# V1b.net
KiCad netlist of a schematic drawn in EAGLE
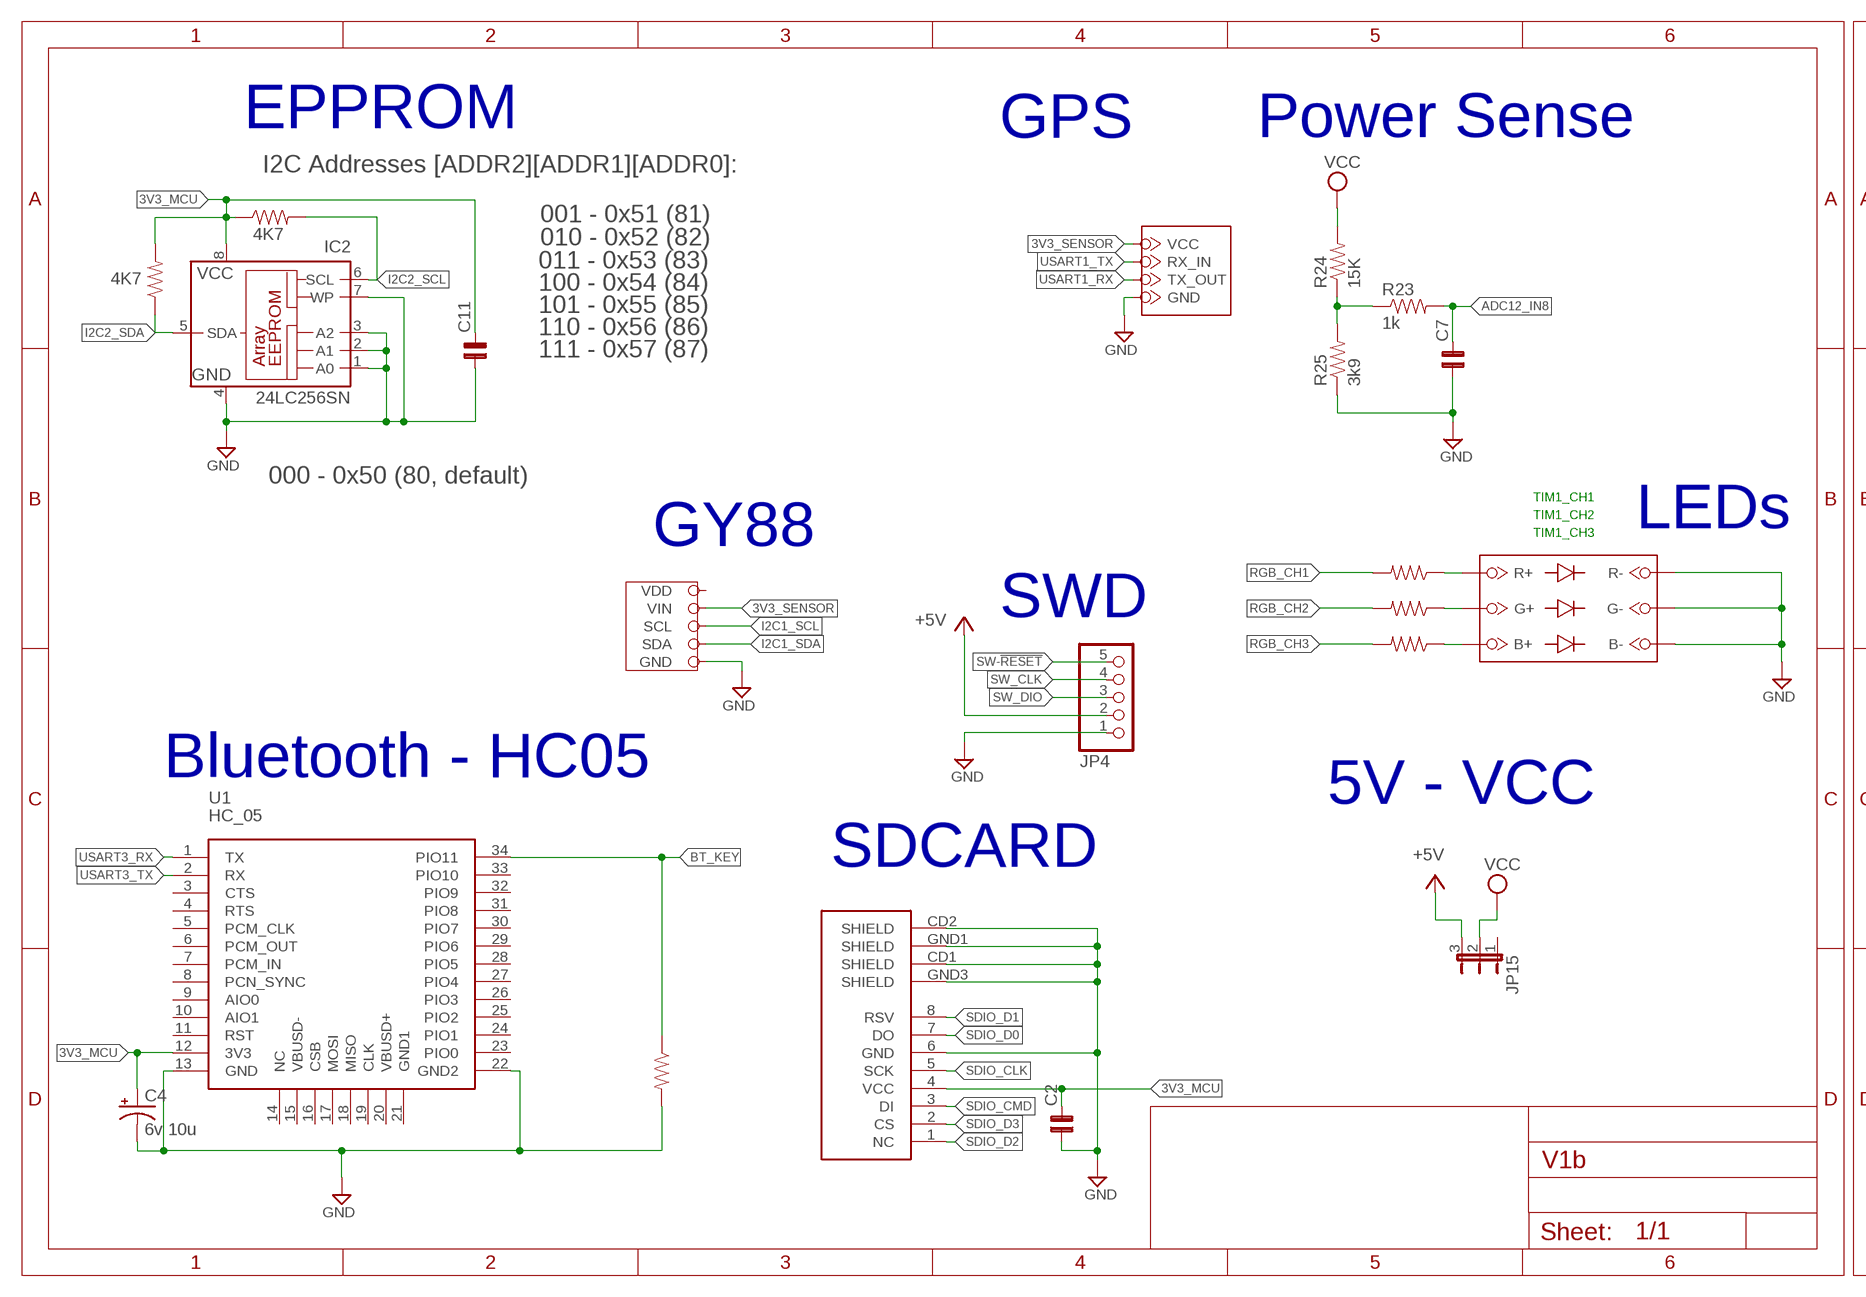
[diagram p0: schematic, sheet 1, part 1 of 2]
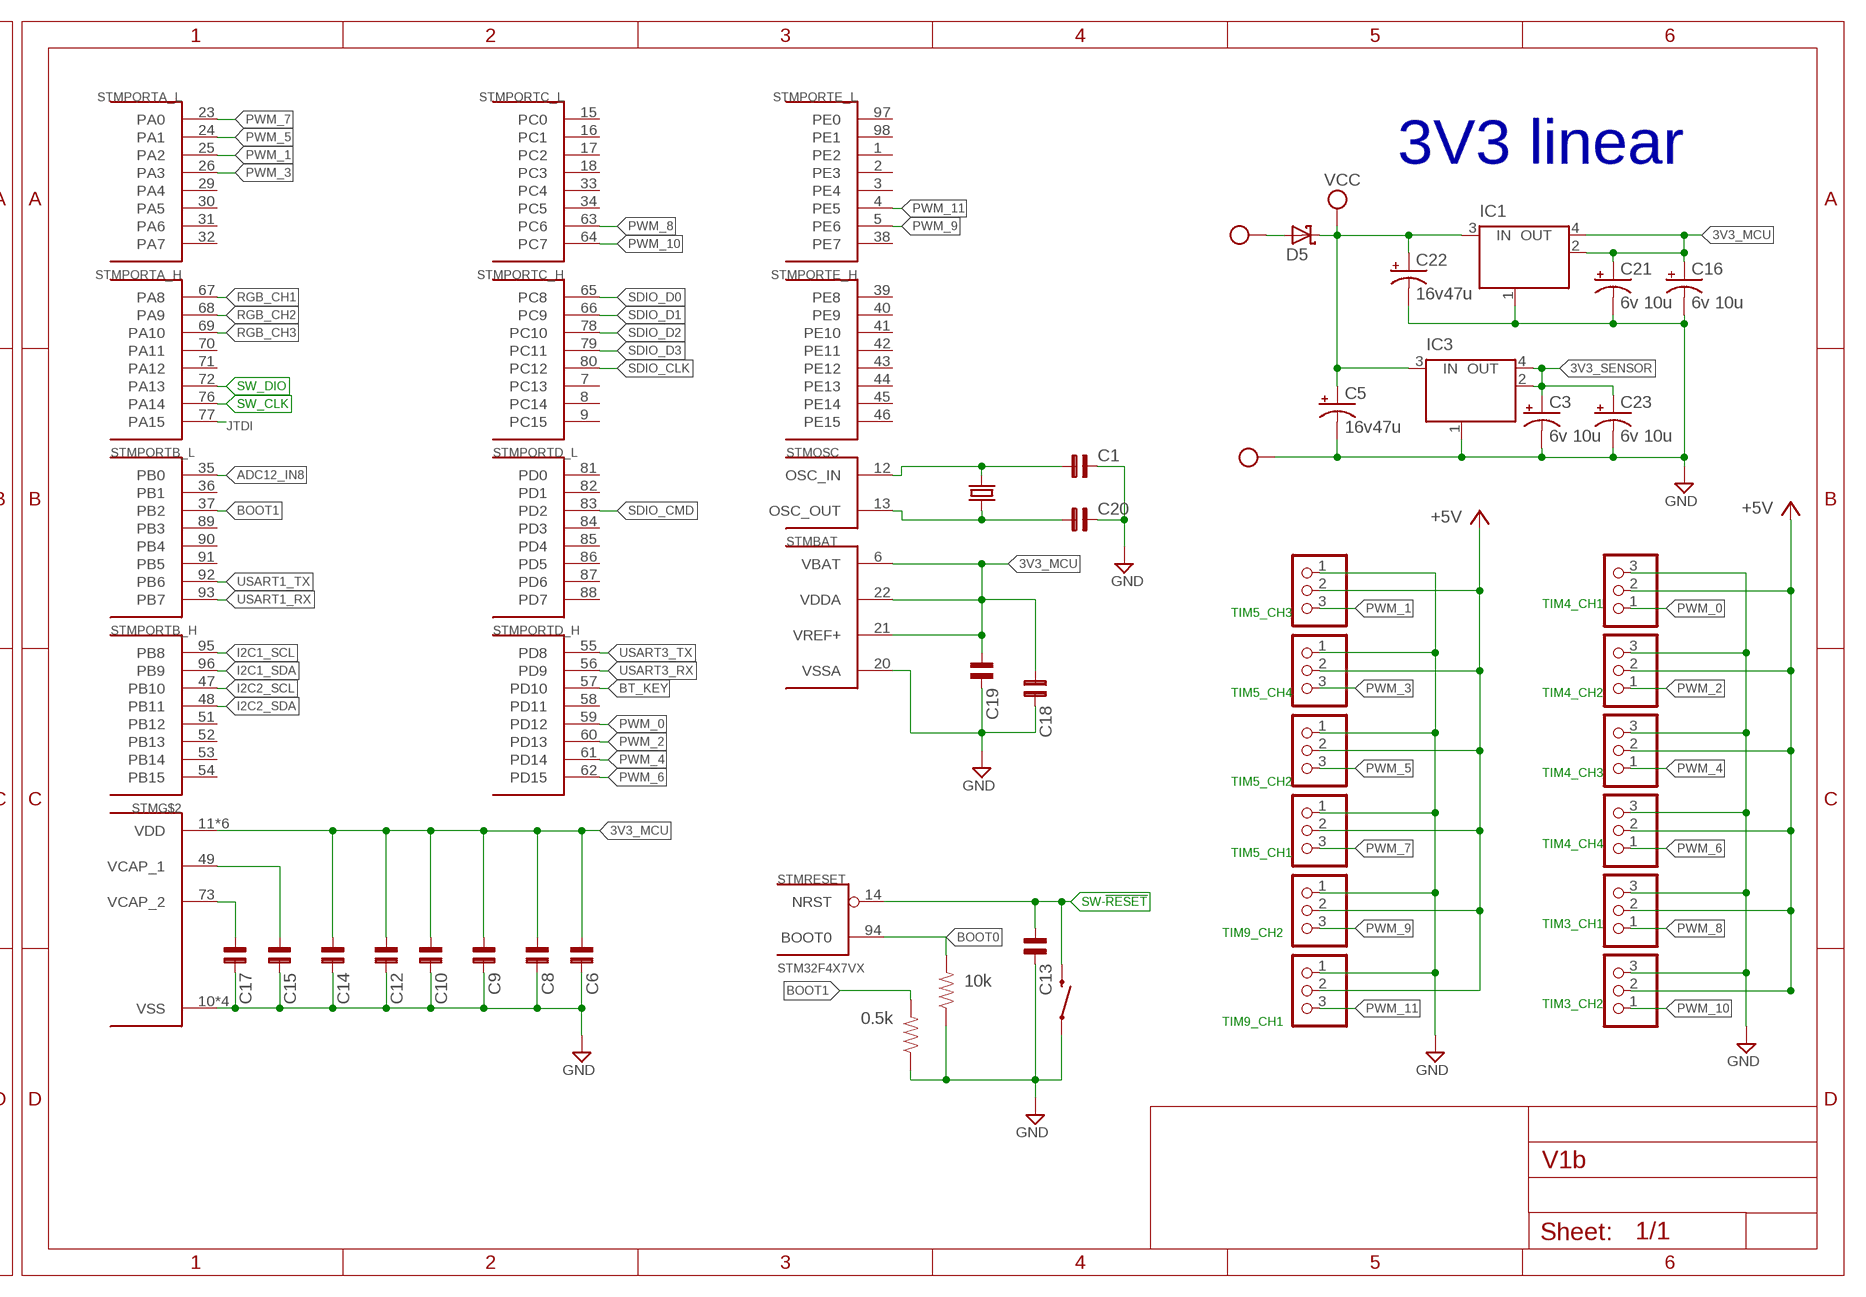
[diagram p1: schematic, sheet 1, part 2 of 2]

(export (version "E")
  (design (tool "Eeschema 10.0.6"))
  (components
    (comp (ref "C1")
      (value "C-NP-SMD-0603")
      (footprint "eagle-import:C-0603")
      (libsource (lib "eagle-import") (part "C-NP-SMD-0603"))
    )
    (comp (ref "C2")
      (value "C-NP-SMD-0603")
      (footprint "eagle-import:C-0603")
      (libsource (lib "eagle-import") (part "C-NP-SMD-0603"))
    )
    (comp (ref "C3")
      (value "6v 10u")
      (footprint "eagle-import:SMC_A")
      (libsource (lib "eagle-import") (part "CPOL-USSMCA"))
    )
    (comp (ref "C4")
      (value "6v 10u")
      (footprint "eagle-import:SMC_A")
      (libsource (lib "eagle-import") (part "CPOL-USSMCA"))
    )
    (comp (ref "C5")
      (value "16v47u")
      (footprint "eagle-import:SMC_C")
      (libsource (lib "eagle-import") (part "CPOL-USSMCC"))
    )
    (comp (ref "C6")
      (value "C-NP-SMD-0603")
      (footprint "eagle-import:C-0603")
      (libsource (lib "eagle-import") (part "C-NP-SMD-0603"))
    )
    (comp (ref "C7")
      (value "C-NP-SMD-0603")
      (footprint "eagle-import:C-0603")
      (libsource (lib "eagle-import") (part "C-NP-SMD-0603"))
    )
    (comp (ref "C8")
      (value "C-NP-SMD-0603")
      (footprint "eagle-import:C-0603")
      (libsource (lib "eagle-import") (part "C-NP-SMD-0603"))
    )
    (comp (ref "C9")
      (value "C-NP-SMD-0603")
      (footprint "eagle-import:C-0603")
      (libsource (lib "eagle-import") (part "C-NP-SMD-0603"))
    )
    (comp (ref "C10")
      (value "C-NP-SMD-0603")
      (footprint "eagle-import:C-0603")
      (libsource (lib "eagle-import") (part "C-NP-SMD-0603"))
    )
    (comp (ref "C11")
      (value "C-NP-SMD-0603")
      (footprint "eagle-import:C-0603")
      (libsource (lib "eagle-import") (part "C-NP-SMD-0603"))
    )
    (comp (ref "C12")
      (value "C-NP-SMD-0603")
      (footprint "eagle-import:C-0603")
      (libsource (lib "eagle-import") (part "C-NP-SMD-0603"))
    )
    (comp (ref "C13")
      (value "C-NP-SMD-0603")
      (footprint "eagle-import:C-0603")
      (libsource (lib "eagle-import") (part "C-NP-SMD-0603"))
    )
    (comp (ref "C14")
      (value "C-NP-SMD-0603")
      (footprint "eagle-import:C-0603")
      (libsource (lib "eagle-import") (part "C-NP-SMD-0603"))
    )
    (comp (ref "C15")
      (value "C-NP-SMD-0603")
      (footprint "eagle-import:C-0603")
      (libsource (lib "eagle-import") (part "C-NP-SMD-0603"))
    )
    (comp (ref "C16")
      (value "6v 10u")
      (footprint "eagle-import:SMC_A")
      (libsource (lib "eagle-import") (part "CPOL-USSMCA"))
    )
    (comp (ref "C17")
      (value "C-NP-SMD-0603")
      (footprint "eagle-import:C-0603")
      (libsource (lib "eagle-import") (part "C-NP-SMD-0603"))
    )
    (comp (ref "C18")
      (value "C-NP-SMD-0603")
      (footprint "eagle-import:C-0603")
      (libsource (lib "eagle-import") (part "C-NP-SMD-0603"))
    )
    (comp (ref "C19")
      (value "C-NP-SMD-0603")
      (footprint "eagle-import:C-0603")
      (libsource (lib "eagle-import") (part "C-NP-SMD-0603"))
    )
    (comp (ref "C20")
      (value "C-NP-SMD-0603")
      (footprint "eagle-import:C-0603")
      (libsource (lib "eagle-import") (part "C-NP-SMD-0603"))
    )
    (comp (ref "C21")
      (value "6v 10u")
      (footprint "eagle-import:SMC_A")
      (libsource (lib "eagle-import") (part "CPOL-USSMCA"))
    )
    (comp (ref "C22")
      (value "16v47u")
      (footprint "eagle-import:SMC_C")
      (libsource (lib "eagle-import") (part "CPOL-USSMCC"))
    )
    (comp (ref "C23")
      (value "6v 10u")
      (footprint "eagle-import:SMC_A")
      (libsource (lib "eagle-import") (part "CPOL-USSMCA"))
    )
    (comp (ref "D5")
      (value "MBRS330T3")
      (footprint "eagle-import:SMC")
      (libsource (lib "eagle-import") (part "MBRS30T33"))
    )
    (comp (ref "IC1")
      (value "LINEAR_MC33269ST-3.3T3")
      (footprint "eagle-import:LINEAR_SOT223")
      (libsource (lib "eagle-import") (part "LINEAR_MC33269ST-3.3T3"))
    )
    (comp (ref "IC2")
      (value "24LC256SN")
      (footprint "eagle-import:SO-08")
      (fields (field (name "MF") "MICROCHIP") (field (name "MPN") "24LC256-I/SN"))
      (libsource (lib "eagle-import") (part "24SNLC256"))
    )
    (comp (ref "IC3")
      (value "LINEAR_MC33269ST-3.3T3")
      (footprint "eagle-import:LINEAR_SOT223")
      (libsource (lib "eagle-import") (part "LINEAR_MC33269ST-3.3T3"))
    )
    (comp (ref "JP1")
      (value "PINHD-1X3_2.54-90°")
      (footprint "eagle-import:1X03_90")
      (libsource (lib "eagle-import") (part "PINHD-1X3_2.54-90°"))
    )
    (comp (ref "JP2")
      (value "PINHD-1X3_2.54-90°")
      (footprint "eagle-import:1X03_90")
      (libsource (lib "eagle-import") (part "PINHD-1X3_2.54-90°"))
    )
    (comp (ref "JP4")
      (value "PINHD-1X5_2.54-90°")
      (footprint "eagle-import:1X05_90")
      (libsource (lib "eagle-import") (part "PINHD-1X5_2.54-90°"))
    )
    (comp (ref "JP5")
      (value "PINHD-1X3_2.54-90°")
      (footprint "eagle-import:1X03_90")
      (libsource (lib "eagle-import") (part "PINHD-1X3_2.54-90°"))
    )
    (comp (ref "JP6")
      (value "PINHD-1X3_2.54-90°")
      (footprint "eagle-import:1X03_90")
      (libsource (lib "eagle-import") (part "PINHD-1X3_2.54-90°"))
    )
    (comp (ref "JP7")
      (value "PINHD-1X3_2.54-90°")
      (footprint "eagle-import:1X03_90")
      (libsource (lib "eagle-import") (part "PINHD-1X3_2.54-90°"))
    )
    (comp (ref "JP8")
      (value "PINHD-1X3_2.54-90°")
      (footprint "eagle-import:1X03_90")
      (libsource (lib "eagle-import") (part "PINHD-1X3_2.54-90°"))
    )
    (comp (ref "JP9")
      (value "PINHD-1X3_2.54-90°")
      (footprint "eagle-import:1X03_90")
      (libsource (lib "eagle-import") (part "PINHD-1X3_2.54-90°"))
    )
    (comp (ref "JP10")
      (value "PINHD-1X3_2.54-90°")
      (footprint "eagle-import:1X03_90")
      (libsource (lib "eagle-import") (part "PINHD-1X3_2.54-90°"))
    )
    (comp (ref "JP11")
      (value "PINHD-1X3_2.54-90°")
      (footprint "eagle-import:1X03_90")
      (libsource (lib "eagle-import") (part "PINHD-1X3_2.54-90°"))
    )
    (comp (ref "JP12")
      (value "PINHD-1X3_2.54-90°")
      (footprint "eagle-import:1X03_90")
      (libsource (lib "eagle-import") (part "PINHD-1X3_2.54-90°"))
    )
    (comp (ref "JP13")
      (value "PINHD-1X3_2.54-90°")
      (footprint "eagle-import:1X03_90")
      (libsource (lib "eagle-import") (part "PINHD-1X3_2.54-90°"))
    )
    (comp (ref "JP14")
      (value "PINHD-1X3_2.54-90°")
      (footprint "eagle-import:1X03_90")
      (libsource (lib "eagle-import") (part "PINHD-1X3_2.54-90°"))
    )
    (comp (ref "JP15")
      (value "JP2E")
      (footprint "eagle-import:JP2")
      (libsource (lib "eagle-import") (part "JP2E"))
    )
    (comp (ref "R2")
      (value "10K")
      (footprint "eagle-import:SPARKFUN_0603-RES")
      (libsource (lib "eagle-import") (part "SPARKFUN_RESISTOR0603-RES"))
    )
    (comp (ref "R3")
      (value "10K")
      (footprint "eagle-import:SPARKFUN_0603-RES")
      (libsource (lib "eagle-import") (part "SPARKFUN_RESISTOR0603-RES"))
    )
    (comp (ref "R5")
      (value "10K")
      (footprint "eagle-import:SPARKFUN_0603-RES")
      (libsource (lib "eagle-import") (part "SPARKFUN_RESISTOR0603-RES"))
    )
    (comp (ref "R6")
      (value "10K")
      (footprint "eagle-import:SPARKFUN_0603-RES")
      (libsource (lib "eagle-import") (part "SPARKFUN_RESISTOR0603-RES"))
    )
    (comp (ref "R7")
      (value "10k")
      (footprint "eagle-import:SPARKFUN_0603-RES")
      (libsource (lib "eagle-import") (part "SPARKFUN_RESISTOR0603-RES"))
    )
    (comp (ref "R8")
      (value "0.5k")
      (footprint "eagle-import:SPARKFUN_0603-RES")
      (libsource (lib "eagle-import") (part "SPARKFUN_RESISTOR0603-RES"))
    )
    (comp (ref "R15")
      (value "4K7")
      (footprint "eagle-import:SPARKFUN_0603-RES")
      (libsource (lib "eagle-import") (part "SPARKFUN_RESISTOR0603-RES"))
    )
    (comp (ref "R16")
      (value "4K7")
      (footprint "eagle-import:SPARKFUN_0603-RES")
      (libsource (lib "eagle-import") (part "SPARKFUN_RESISTOR0603-RES"))
    )
    (comp (ref "R23")
      (value "1k")
      (footprint "eagle-import:SPARKFUN_0603-RES")
      (libsource (lib "eagle-import") (part "SPARKFUN_RESISTOR0603-RES"))
    )
    (comp (ref "R24")
      (value "15K")
      (footprint "eagle-import:SPARKFUN_0603-RES")
      (libsource (lib "eagle-import") (part "SPARKFUN_RESISTOR0603-RES"))
    )
    (comp (ref "R25")
      (value "3k9")
      (footprint "eagle-import:SPARKFUN_0603-RES")
      (libsource (lib "eagle-import") (part "SPARKFUN_RESISTOR0603-RES"))
    )
    (comp (ref "S1")
      (value "RESET")
      (footprint "eagle-import:TACTILE-SWITCH-1101NE")
      (fields (field (name "PARTNO") "EVQ-P7J01P"))
      (libsource (lib "eagle-import") (part "SWITCH-MOMENTARY-2-SMD-1101NE"))
    )
    (comp (ref "SDCARD2")
      (value "microSD Socket")
      (footprint "eagle-import:MICRO-SD-SOCKET-PP")
      (libsource (lib "eagle-import") (part "USD-SOCKETNEW"))
    )
    (comp (ref "STM")
      (value "STM32F4X7VX")
      (footprint "eagle-import:TQFP100")
      (fields (field (name "PARTNO") "STM32F427VI"))
      (libsource (lib "eagle-import") (part "STM32F4X7VX"))
    )
    (comp (ref "U$1")
      (value "GY-88")
      (footprint "eagle-import:BREAKOUT")
      (libsource (lib "eagle-import") (part "GY-88"))
    )
    (comp (ref "U$8")
      (value "RGB_LED")
      (footprint "eagle-import:SMD")
      (libsource (lib "eagle-import") (part "RGB_LED"))
    )
    (comp (ref "U$10")
      (value "GPS_MODULE")
      (footprint "eagle-import:23X30")
      (libsource (lib "eagle-import") (part "GPS_MODULE"))
    )
    (comp (ref "U1")
      (value "HC_05")
      (footprint "eagle-import:BLUETOOTH_SMD")
      (libsource (lib "eagle-import") (part "HC_05"))
    )
    (comp (ref "X1")
      (value "MKDSN1,5/2-5,08")
      (footprint "eagle-import:MKDSN1,5_2-5,08")
      (fields (field (name "MPN") "MKDSN 1,5/2-5.08"))
      (libsource (lib "eagle-import") (part "MKDSN1,5/2-5,08"))
    )
    (comp (ref "Y1")
      (value "CRYSTALHC49US")
      (footprint "eagle-import:HC49US")
      (libsource (lib "eagle-import") (part "CRYSTALHC49US"))
    )
  )
  (nets
    (net (code "1") (name "+5V") (class "Default")
      (node (ref "JP1") (pin "2") (pinfunction "2_2") (pintype "passive"))
      (node (ref "JP10") (pin "2") (pinfunction "2_2") (pintype "passive"))
      (node (ref "JP11") (pin "2") (pinfunction "2_2") (pintype "passive"))
      (node (ref "JP12") (pin "2") (pinfunction "2_2") (pintype "passive"))
      (node (ref "JP13") (pin "2") (pinfunction "2_2") (pintype "passive"))
      (node (ref "JP14") (pin "2") (pinfunction "2_2") (pintype "passive"))
      (node (ref "JP15") (pin "3") (pinfunction "3_3") (pintype "passive"))
      (node (ref "JP2") (pin "2") (pinfunction "2_2") (pintype "passive"))
      (node (ref "JP4") (pin "2") (pinfunction "2_2") (pintype "passive"))
      (node (ref "JP5") (pin "2") (pinfunction "2_2") (pintype "passive"))
      (node (ref "JP6") (pin "2") (pinfunction "2_2") (pintype "passive"))
      (node (ref "JP7") (pin "2") (pinfunction "2_2") (pintype "passive"))
      (node (ref "JP8") (pin "2") (pinfunction "2_2") (pintype "passive"))
      (node (ref "JP9") (pin "2") (pinfunction "2_2") (pintype "passive"))
    )
    (net (code "2") (name "/JTDI") (class "Default")
      (node (ref "STM") (pin "77") (pinfunction "PA15_77") (pintype "bidirectional"))
    )
    (net (code "3") (name "/SW-~{RESET}") (class "Default")
      (node (ref "C13") (pin "1") (pinfunction "1_1") (pintype "passive"))
      (node (ref "JP4") (pin "5") (pinfunction "5_5") (pintype "passive"))
      (node (ref "S1") (pin "P$2") (pinfunction "2_P$2") (pintype "passive"))
      (node (ref "STM") (pin "14") (pinfunction "NRST_14") (pintype "input"))
    )
    (net (code "4") (name "3V3_MCU") (class "Default")
      (node (ref "C10") (pin "1") (pinfunction "1_1") (pintype "passive"))
      (node (ref "C11") (pin "2") (pinfunction "2_2") (pintype "passive"))
      (node (ref "C12") (pin "1") (pinfunction "1_1") (pintype "passive"))
      (node (ref "C14") (pin "1") (pinfunction "1_1") (pintype "passive"))
      (node (ref "C16") (pin "+") (pinfunction "+_+") (pintype "passive"))
      (node (ref "C18") (pin "1") (pinfunction "1_1") (pintype "passive"))
      (node (ref "C19") (pin "1") (pinfunction "1_1") (pintype "passive"))
      (node (ref "C2") (pin "2") (pinfunction "2_2") (pintype "passive"))
      (node (ref "C21") (pin "+") (pinfunction "+_+") (pintype "passive"))
      (node (ref "C4") (pin "+") (pinfunction "+_+") (pintype "passive"))
      (node (ref "C6") (pin "1") (pinfunction "1_1") (pintype "passive"))
      (node (ref "C8") (pin "1") (pinfunction "1_1") (pintype "passive"))
      (node (ref "C9") (pin "1") (pinfunction "1_1") (pintype "passive"))
      (node (ref "IC1") (pin "2") (pinfunction "OUT_2") (pintype "passive"))
      (node (ref "IC1") (pin "4") (pinfunction "OUT_4") (pintype "passive"))
      (node (ref "IC2") (pin "8") (pinfunction "VCC_8") (pintype "power_in"))
      (node (ref "R15") (pin "1") (pinfunction "1_1") (pintype "passive"))
      (node (ref "R16") (pin "2") (pinfunction "2_2") (pintype "passive"))
      (node (ref "SDCARD2") (pin "4") (pinfunction "VCC_4") (pintype "bidirectional"))
      (node (ref "STM") (pin "100") (pinfunction "VDD_100") (pintype "power_in"))
      (node (ref "STM") (pin "11") (pinfunction "VDD_11") (pintype "power_in"))
      (node (ref "STM") (pin "19") (pinfunction "VDD_19") (pintype "power_in"))
      (node (ref "STM") (pin "21") (pinfunction "VREF+_21") (pintype "input"))
      (node (ref "STM") (pin "22") (pinfunction "VDDA_22") (pintype "power_in"))
      (node (ref "STM") (pin "28") (pinfunction "VDD_28") (pintype "power_in"))
      (node (ref "STM") (pin "50") (pinfunction "VDD_50") (pintype "power_in"))
      (node (ref "STM") (pin "6") (pinfunction "VBAT_6") (pintype "power_in"))
      (node (ref "STM") (pin "75") (pinfunction "VDD_75") (pintype "power_in"))
      (node (ref "U1") (pin "12") (pinfunction "3V3_12") (pintype "bidirectional"))
    )
    (net (code "5") (name "3V3_SENSOR") (class "Default")
      (node (ref "C23") (pin "+") (pinfunction "+_+") (pintype "passive"))
      (node (ref "C3") (pin "+") (pinfunction "+_+") (pintype "passive"))
      (node (ref "IC3") (pin "2") (pinfunction "OUT_2") (pintype "passive"))
      (node (ref "IC3") (pin "4") (pinfunction "OUT_4") (pintype "passive"))
      (node (ref "U$1") (pin "2") (pinfunction "VIN_2") (pintype "bidirectional"))
      (node (ref "U$10") (pin "4") (pinfunction "VCC_4") (pintype "bidirectional"))
    )
    (net (code "6") (name "ADC12_IN8") (class "Default")
      (node (ref "C7") (pin "2") (pinfunction "2_2") (pintype "passive"))
      (node (ref "R23") (pin "2") (pinfunction "2_2") (pintype "passive"))
      (node (ref "STM") (pin "35") (pinfunction "PB0_35") (pintype "bidirectional"))
    )
    (net (code "7") (name "BOOT0") (class "Default")
      (node (ref "R7") (pin "2") (pinfunction "2_2") (pintype "passive"))
      (node (ref "STM") (pin "94") (pinfunction "BOOT0_94") (pintype "input"))
    )
    (net (code "8") (name "BOOT1") (class "Default")
      (node (ref "R8") (pin "2") (pinfunction "2_2") (pintype "passive"))
      (node (ref "STM") (pin "37") (pinfunction "PB2_37") (pintype "bidirectional"))
    )
    (net (code "9") (name "BT_KEY") (class "Default")
      (node (ref "R5") (pin "1") (pinfunction "1_1") (pintype "passive"))
      (node (ref "STM") (pin "57") (pinfunction "PD10_57") (pintype "bidirectional"))
      (node (ref "U1") (pin "34") (pinfunction "PIO11_34") (pintype "bidirectional"))
    )
    (net (code "10") (name "GND") (class "Default")
      (node (ref "C1") (pin "2") (pinfunction "2_2") (pintype "passive"))
      (node (ref "C10") (pin "2") (pinfunction "2_2") (pintype "passive"))
      (node (ref "C11") (pin "1") (pinfunction "1_1") (pintype "passive"))
      (node (ref "C12") (pin "2") (pinfunction "2_2") (pintype "passive"))
      (node (ref "C13") (pin "2") (pinfunction "2_2") (pintype "passive"))
      (node (ref "C14") (pin "2") (pinfunction "2_2") (pintype "passive"))
      (node (ref "C15") (pin "2") (pinfunction "2_2") (pintype "passive"))
      (node (ref "C16") (pin "-") (pinfunction "-_-") (pintype "passive"))
      (node (ref "C17") (pin "2") (pinfunction "2_2") (pintype "passive"))
      (node (ref "C18") (pin "2") (pinfunction "2_2") (pintype "passive"))
      (node (ref "C19") (pin "2") (pinfunction "2_2") (pintype "passive"))
      (node (ref "C2") (pin "1") (pinfunction "1_1") (pintype "passive"))
      (node (ref "C20") (pin "2") (pinfunction "2_2") (pintype "passive"))
      (node (ref "C21") (pin "-") (pinfunction "-_-") (pintype "passive"))
      (node (ref "C22") (pin "-") (pinfunction "-_-") (pintype "passive"))
      (node (ref "C23") (pin "-") (pinfunction "-_-") (pintype "passive"))
      (node (ref "C3") (pin "-") (pinfunction "-_-") (pintype "passive"))
      (node (ref "C4") (pin "-") (pinfunction "-_-") (pintype "passive"))
      (node (ref "C5") (pin "-") (pinfunction "-_-") (pintype "passive"))
      (node (ref "C6") (pin "2") (pinfunction "2_2") (pintype "passive"))
      (node (ref "C7") (pin "1") (pinfunction "1_1") (pintype "passive"))
      (node (ref "C8") (pin "2") (pinfunction "2_2") (pintype "passive"))
      (node (ref "C9") (pin "2") (pinfunction "2_2") (pintype "passive"))
      (node (ref "IC1") (pin "1") (pinfunction "GND/ADJ_1") (pintype "input"))
      (node (ref "IC2") (pin "1") (pinfunction "A0_1") (pintype "input"))
      (node (ref "IC2") (pin "2") (pinfunction "A1_2") (pintype "input"))
      (node (ref "IC2") (pin "3") (pinfunction "A2_3") (pintype "input"))
      (node (ref "IC2") (pin "4") (pinfunction "GND_4") (pintype "power_in"))
      (node (ref "IC2") (pin "7") (pinfunction "WP_7") (pintype "input"))
      (node (ref "IC3") (pin "1") (pinfunction "GND/ADJ_1") (pintype "input"))
      (node (ref "JP1") (pin "1") (pinfunction "1_1") (pintype "passive"))
      (node (ref "JP10") (pin "3") (pinfunction "3_3") (pintype "passive"))
      (node (ref "JP11") (pin "1") (pinfunction "1_1") (pintype "passive"))
      (node (ref "JP12") (pin "3") (pinfunction "3_3") (pintype "passive"))
      (node (ref "JP13") (pin "3") (pinfunction "3_3") (pintype "passive"))
      (node (ref "JP14") (pin "3") (pinfunction "3_3") (pintype "passive"))
      (node (ref "JP2") (pin "1") (pinfunction "1_1") (pintype "passive"))
      (node (ref "JP4") (pin "1") (pinfunction "1_1") (pintype "passive"))
      (node (ref "JP5") (pin "1") (pinfunction "1_1") (pintype "passive"))
      (node (ref "JP6") (pin "1") (pinfunction "1_1") (pintype "passive"))
      (node (ref "JP7") (pin "3") (pinfunction "3_3") (pintype "passive"))
      (node (ref "JP8") (pin "1") (pinfunction "1_1") (pintype "passive"))
      (node (ref "JP9") (pin "3") (pinfunction "3_3") (pintype "passive"))
      (node (ref "R25") (pin "1") (pinfunction "1_1") (pintype "passive"))
      (node (ref "R5") (pin "2") (pinfunction "2_2") (pintype "passive"))
      (node (ref "R7") (pin "1") (pinfunction "1_1") (pintype "passive"))
      (node (ref "R8") (pin "1") (pinfunction "1_1") (pintype "passive"))
      (node (ref "S1") (pin "P$1") (pinfunction "1_P$1") (pintype "passive"))
      (node (ref "SDCARD2") (pin "6") (pinfunction "GND_6") (pintype "bidirectional"))
      (node (ref "SDCARD2") (pin "CD1") (pinfunction "SHIELD_CD1") (pintype "bidirectional"))
      (node (ref "SDCARD2") (pin "CD2") (pinfunction "SHIELD_CD2") (pintype "bidirectional"))
      (node (ref "SDCARD2") (pin "GND1") (pinfunction "SHIELD_GND1") (pintype "bidirectional"))
      (node (ref "SDCARD2") (pin "GND3") (pinfunction "SHIELD_GND3") (pintype "bidirectional"))
      (node (ref "STM") (pin "10") (pinfunction "VSS_10") (pintype "power_in"))
      (node (ref "STM") (pin "20") (pinfunction "VSSA_20") (pintype "power_in"))
      (node (ref "STM") (pin "27") (pinfunction "VSS_27") (pintype "power_in"))
      (node (ref "STM") (pin "74") (pinfunction "VSS_74") (pintype "power_in"))
      (node (ref "STM") (pin "99") (pinfunction "VSS_99") (pintype "power_in"))
      (node (ref "U$1") (pin "3") (pinfunction "GND_3") (pintype "bidirectional"))
      (node (ref "U$10") (pin "1") (pinfunction "GND_1") (pintype "bidirectional"))
      (node (ref "U$8") (pin "B-") (pinfunction "B-_B-") (pintype "bidirectional"))
      (node (ref "U$8") (pin "G-") (pinfunction "G-_G-") (pintype "bidirectional"))
      (node (ref "U$8") (pin "R-") (pinfunction "R-_R-") (pintype "bidirectional"))
      (node (ref "U1") (pin "13") (pinfunction "GND_13") (pintype "bidirectional"))
      (node (ref "U1") (pin "22") (pinfunction "GND2_22") (pintype "bidirectional"))
      (node (ref "X1") (pin "2") (pinfunction "KL_2") (pintype "passive"))
    )
    (net (code "11") (name "I2C1_SCL") (class "Default")
      (node (ref "STM") (pin "95") (pinfunction "PB8_95") (pintype "bidirectional"))
      (node (ref "U$1") (pin "4") (pinfunction "SCL_4") (pintype "bidirectional"))
    )
    (net (code "12") (name "I2C1_SDA") (class "Default")
      (node (ref "STM") (pin "96") (pinfunction "PB9_96") (pintype "bidirectional"))
      (node (ref "U$1") (pin "5") (pinfunction "SDA_5") (pintype "bidirectional"))
    )
    (net (code "13") (name "I2C2_SCL") (class "Default")
      (node (ref "IC2") (pin "6") (pinfunction "SCL_6") (pintype "input"))
      (node (ref "R15") (pin "2") (pinfunction "2_2") (pintype "passive"))
      (node (ref "STM") (pin "47") (pinfunction "PB10_47") (pintype "bidirectional"))
    )
    (net (code "14") (name "I2C2_SDA") (class "Default")
      (node (ref "IC2") (pin "5") (pinfunction "SDA_5") (pintype "bidirectional"))
      (node (ref "R16") (pin "1") (pinfunction "1_1") (pintype "passive"))
      (node (ref "STM") (pin "48") (pinfunction "PB11_48") (pintype "bidirectional"))
    )
    (net (code "15") (name "Net-(R2-Pad1)") (class "Default")
      (node (ref "R2") (pin "1") (pinfunction "1_1") (pintype "passive"))
      (node (ref "U$8") (pin "B+") (pinfunction "B+_B+") (pintype "bidirectional"))
    )
    (net (code "16") (name "Net-(R3-Pad1)") (class "Default")
      (node (ref "R3") (pin "1") (pinfunction "1_1") (pintype "passive"))
      (node (ref "U$8") (pin "G+") (pinfunction "G+_G+") (pintype "bidirectional"))
    )
    (net (code "17") (name "Net-(R6-Pad1)") (class "Default")
      (node (ref "R6") (pin "1") (pinfunction "1_1") (pintype "passive"))
      (node (ref "U$8") (pin "R+") (pinfunction "R+_R+") (pintype "bidirectional"))
    )
    (net (code "18") (name "Net-(R23-Pad1)") (class "Default")
      (node (ref "R23") (pin "1") (pinfunction "1_1") (pintype "passive"))
      (node (ref "R24") (pin "1") (pinfunction "1_1") (pintype "passive"))
      (node (ref "R25") (pin "2") (pinfunction "2_2") (pintype "passive"))
    )
    (net (code "19") (name "Net-(STMB-VCAP_1)") (class "Default")
      (node (ref "C15") (pin "1") (pinfunction "1_1") (pintype "passive"))
      (node (ref "STM") (pin "49") (pinfunction "VCAP_1_49") (pintype "power_in"))
    )
    (net (code "20") (name "Net-(STMB-VCAP_2)") (class "Default")
      (node (ref "C17") (pin "1") (pinfunction "1_1") (pintype "passive"))
      (node (ref "STM") (pin "73") (pinfunction "VCAP_2_73") (pintype "power_in"))
    )
    (net (code "21") (name "Net-(STMC-OSC_IN)") (class "Default")
      (node (ref "C1") (pin "1") (pinfunction "1_1") (pintype "passive"))
      (node (ref "STM") (pin "12") (pinfunction "OSC_IN_12") (pintype "input"))
      (node (ref "Y1") (pin "2") (pinfunction "2_2") (pintype "passive"))
    )
    (net (code "22") (name "Net-(STMC-OSC_OUT)") (class "Default")
      (node (ref "C20") (pin "1") (pinfunction "1_1") (pintype "passive"))
      (node (ref "STM") (pin "13") (pinfunction "OSC_OUT_13") (pintype "output"))
      (node (ref "Y1") (pin "1") (pinfunction "1_1") (pintype "passive"))
    )
    (net (code "23") (name "Net-(X1A-KL)") (class "Default")
      (node (ref "D5") (pin "A") (pinfunction "A_A") (pintype "passive"))
      (node (ref "X1") (pin "1") (pinfunction "KL_1") (pintype "passive"))
    )
    (net (code "24") (name "PWM_0") (class "Default")
      (node (ref "JP7") (pin "1") (pinfunction "1_1") (pintype "passive"))
      (node (ref "STM") (pin "59") (pinfunction "PD12_59") (pintype "bidirectional"))
    )
    (net (code "25") (name "PWM_1") (class "Default")
      (node (ref "JP11") (pin "3") (pinfunction "3_3") (pintype "passive"))
      (node (ref "STM") (pin "25") (pinfunction "PA2_25") (pintype "bidirectional"))
    )
    (net (code "26") (name "PWM_2") (class "Default")
      (node (ref "JP9") (pin "1") (pinfunction "1_1") (pintype "passive"))
      (node (ref "STM") (pin "60") (pinfunction "PD13_60") (pintype "bidirectional"))
    )
    (net (code "27") (name "PWM_3") (class "Default")
      (node (ref "JP6") (pin "3") (pinfunction "3_3") (pintype "passive"))
      (node (ref "STM") (pin "26") (pinfunction "PA3_26") (pintype "bidirectional"))
    )
    (net (code "28") (name "PWM_4") (class "Default")
      (node (ref "JP10") (pin "1") (pinfunction "1_1") (pintype "passive"))
      (node (ref "STM") (pin "61") (pinfunction "PD14_61") (pintype "bidirectional"))
    )
    (net (code "29") (name "PWM_5") (class "Default")
      (node (ref "JP5") (pin "3") (pinfunction "3_3") (pintype "passive"))
      (node (ref "STM") (pin "24") (pinfunction "PA1_24") (pintype "bidirectional"))
    )
    (net (code "30") (name "PWM_6") (class "Default")
      (node (ref "JP12") (pin "1") (pinfunction "1_1") (pintype "passive"))
      (node (ref "STM") (pin "62") (pinfunction "PD15_62") (pintype "bidirectional"))
    )
    (net (code "31") (name "PWM_7") (class "Default")
      (node (ref "JP1") (pin "3") (pinfunction "3_3") (pintype "passive"))
      (node (ref "STM") (pin "23") (pinfunction "PA0_23") (pintype "bidirectional"))
    )
    (net (code "32") (name "PWM_8") (class "Default")
      (node (ref "JP13") (pin "1") (pinfunction "1_1") (pintype "passive"))
      (node (ref "STM") (pin "63") (pinfunction "PC6_63") (pintype "bidirectional"))
    )
    (net (code "33") (name "PWM_9") (class "Default")
      (node (ref "JP8") (pin "3") (pinfunction "3_3") (pintype "passive"))
      (node (ref "STM") (pin "5") (pinfunction "PE6_5") (pintype "bidirectional"))
    )
    (net (code "34") (name "PWM_10") (class "Default")
      (node (ref "JP14") (pin "1") (pinfunction "1_1") (pintype "passive"))
      (node (ref "STM") (pin "64") (pinfunction "PC7_64") (pintype "bidirectional"))
    )
    (net (code "35") (name "PWM_11") (class "Default")
      (node (ref "JP2") (pin "3") (pinfunction "3_3") (pintype "passive"))
      (node (ref "STM") (pin "4") (pinfunction "PE5_4") (pintype "bidirectional"))
    )
    (net (code "36") (name "RGB_CH1") (class "Default")
      (node (ref "R6") (pin "2") (pinfunction "2_2") (pintype "passive"))
      (node (ref "STM") (pin "67") (pinfunction "PA8_67") (pintype "bidirectional"))
    )
    (net (code "37") (name "RGB_CH2") (class "Default")
      (node (ref "R3") (pin "2") (pinfunction "2_2") (pintype "passive"))
      (node (ref "STM") (pin "68") (pinfunction "PA9_68") (pintype "bidirectional"))
    )
    (net (code "38") (name "RGB_CH3") (class "Default")
      (node (ref "R2") (pin "2") (pinfunction "2_2") (pintype "passive"))
      (node (ref "STM") (pin "69") (pinfunction "PA10_69") (pintype "bidirectional"))
    )
    (net (code "39") (name "SDIO_CLK") (class "Default")
      (node (ref "SDCARD2") (pin "5") (pinfunction "SCK_5") (pintype "bidirectional"))
      (node (ref "STM") (pin "80") (pinfunction "PC12_80") (pintype "bidirectional"))
    )
    (net (code "40") (name "SDIO_CMD") (class "Default")
      (node (ref "SDCARD2") (pin "3") (pinfunction "DI_3") (pintype "bidirectional"))
      (node (ref "STM") (pin "83") (pinfunction "PD2_83") (pintype "bidirectional"))
    )
    (net (code "41") (name "SDIO_D0") (class "Default")
      (node (ref "SDCARD2") (pin "7") (pinfunction "DO_7") (pintype "bidirectional"))
      (node (ref "STM") (pin "65") (pinfunction "PC8_65") (pintype "bidirectional"))
    )
    (net (code "42") (name "SDIO_D1") (class "Default")
      (node (ref "SDCARD2") (pin "8") (pinfunction "RSV_8") (pintype "bidirectional"))
      (node (ref "STM") (pin "66") (pinfunction "PC9_66") (pintype "bidirectional"))
    )
    (net (code "43") (name "SDIO_D2") (class "Default")
      (node (ref "SDCARD2") (pin "1") (pinfunction "NC_1") (pintype "bidirectional"))
      (node (ref "STM") (pin "78") (pinfunction "PC10_78") (pintype "bidirectional"))
    )
    (net (code "44") (name "SDIO_D3") (class "Default")
      (node (ref "SDCARD2") (pin "2") (pinfunction "CS_2") (pintype "bidirectional"))
      (node (ref "STM") (pin "79") (pinfunction "PC11_79") (pintype "bidirectional"))
    )
    (net (code "45") (name "SW_CLK") (class "Default")
      (node (ref "JP4") (pin "4") (pinfunction "4_4") (pintype "passive"))
      (node (ref "STM") (pin "76") (pinfunction "PA14_76") (pintype "bidirectional"))
    )
    (net (code "46") (name "SW_DIO") (class "Default")
      (node (ref "JP4") (pin "3") (pinfunction "3_3") (pintype "passive"))
      (node (ref "STM") (pin "72") (pinfunction "PA13_72") (pintype "bidirectional"))
    )
    (net (code "47") (name "USART1_RX") (class "Default")
      (node (ref "STM") (pin "93") (pinfunction "PB7_93") (pintype "bidirectional"))
      (node (ref "U$10") (pin "2") (pinfunction "TX_OUT_2") (pintype "bidirectional"))
    )
    (net (code "48") (name "USART1_TX") (class "Default")
      (node (ref "STM") (pin "92") (pinfunction "PB6_92") (pintype "bidirectional"))
      (node (ref "U$10") (pin "3") (pinfunction "RX_IN_3") (pintype "bidirectional"))
    )
    (net (code "49") (name "USART3_RX") (class "Default")
      (node (ref "STM") (pin "56") (pinfunction "PD9_56") (pintype "bidirectional"))
      (node (ref "U1") (pin "1") (pinfunction "TX_1") (pintype "bidirectional"))
    )
    (net (code "50") (name "USART3_TX") (class "Default")
      (node (ref "STM") (pin "55") (pinfunction "PD8_55") (pintype "bidirectional"))
      (node (ref "U1") (pin "2") (pinfunction "RX_2") (pintype "bidirectional"))
    )
    (net (code "51") (name "VCC") (class "Default")
      (node (ref "C22") (pin "+") (pinfunction "+_+") (pintype "passive"))
      (node (ref "C5") (pin "+") (pinfunction "+_+") (pintype "passive"))
      (node (ref "D5") (pin "C") (pinfunction "C_C") (pintype "passive"))
      (node (ref "IC1") (pin "3") (pinfunction "IN_3") (pintype "input"))
      (node (ref "IC3") (pin "3") (pinfunction "IN_3") (pintype "input"))
      (node (ref "JP15") (pin "2") (pinfunction "2_2") (pintype "passive"))
      (node (ref "R24") (pin "2") (pinfunction "2_2") (pintype "passive"))
    )
    (net (code "52") (name "unconnected-(JP15-Pad1)") (class "Default")
      (node (ref "JP15") (pin "1") (pinfunction "1_1") (pintype "passive"))
    )
    (net (code "53") (name "unconnected-(STMD-PA11-Pad70)") (class "Default")
      (node (ref "STM") (pin "70") (pinfunction "PA11_70") (pintype "bidirectional"))
    )
    (net (code "54") (name "unconnected-(STMD-PA12-Pad71)") (class "Default")
      (node (ref "STM") (pin "71") (pinfunction "PA12_71") (pintype "bidirectional"))
    )
    (net (code "55") (name "unconnected-(STME-PA4-Pad29)") (class "Default")
      (node (ref "STM") (pin "29") (pinfunction "PA4_29") (pintype "bidirectional"))
    )
    (net (code "56") (name "unconnected-(STME-PA5-Pad30)") (class "Default")
      (node (ref "STM") (pin "30") (pinfunction "PA5_30") (pintype "bidirectional"))
    )
    (net (code "57") (name "unconnected-(STME-PA6-Pad31)") (class "Default")
      (node (ref "STM") (pin "31") (pinfunction "PA6_31") (pintype "bidirectional"))
    )
    (net (code "58") (name "unconnected-(STME-PA7-Pad32)") (class "Default")
      (node (ref "STM") (pin "32") (pinfunction "PA7_32") (pintype "bidirectional"))
    )
    (net (code "59") (name "unconnected-(STMF-PB12-Pad51)") (class "Default")
      (node (ref "STM") (pin "51") (pinfunction "PB12_51") (pintype "bidirectional"))
    )
    (net (code "60") (name "unconnected-(STMF-PB13-Pad52)") (class "Default")
      (node (ref "STM") (pin "52") (pinfunction "PB13_52") (pintype "bidirectional"))
    )
    (net (code "61") (name "unconnected-(STMF-PB14-Pad53)") (class "Default")
      (node (ref "STM") (pin "53") (pinfunction "PB14_53") (pintype "bidirectional"))
    )
    (net (code "62") (name "unconnected-(STMF-PB15-Pad54)") (class "Default")
      (node (ref "STM") (pin "54") (pinfunction "PB15_54") (pintype "bidirectional"))
    )
    (net (code "63") (name "unconnected-(STMG-PB1-Pad36)") (class "Default")
      (node (ref "STM") (pin "36") (pinfunction "PB1_36") (pintype "bidirectional"))
    )
    (net (code "64") (name "unconnected-(STMG-PB3-Pad89)") (class "Default")
      (node (ref "STM") (pin "89") (pinfunction "PB3_89") (pintype "bidirectional"))
    )
    (net (code "65") (name "unconnected-(STMG-PB4-Pad90)") (class "Default")
      (node (ref "STM") (pin "90") (pinfunction "PB4_90") (pintype "bidirectional"))
    )
    (net (code "66") (name "unconnected-(STMG-PB5-Pad91)") (class "Default")
      (node (ref "STM") (pin "91") (pinfunction "PB5_91") (pintype "bidirectional"))
    )
    (net (code "67") (name "unconnected-(STMH-PC13-Pad7)") (class "Default")
      (node (ref "STM") (pin "7") (pinfunction "PC13_7") (pintype "bidirectional"))
    )
    (net (code "68") (name "unconnected-(STMH-PC14-Pad8)") (class "Default")
      (node (ref "STM") (pin "8") (pinfunction "PC14_8") (pintype "bidirectional"))
    )
    (net (code "69") (name "unconnected-(STMH-PC15-Pad9)") (class "Default")
      (node (ref "STM") (pin "9") (pinfunction "PC15_9") (pintype "bidirectional"))
    )
    (net (code "70") (name "unconnected-(STMI-PC0-Pad15)") (class "Default")
      (node (ref "STM") (pin "15") (pinfunction "PC0_15") (pintype "bidirectional"))
    )
    (net (code "71") (name "unconnected-(STMI-PC1-Pad16)") (class "Default")
      (node (ref "STM") (pin "16") (pinfunction "PC1_16") (pintype "bidirectional"))
    )
    (net (code "72") (name "unconnected-(STMI-PC2-Pad17)") (class "Default")
      (node (ref "STM") (pin "17") (pinfunction "PC2_17") (pintype "bidirectional"))
    )
    (net (code "73") (name "unconnected-(STMI-PC3-Pad18)") (class "Default")
      (node (ref "STM") (pin "18") (pinfunction "PC3_18") (pintype "bidirectional"))
    )
    (net (code "74") (name "unconnected-(STMI-PC4-Pad33)") (class "Default")
      (node (ref "STM") (pin "33") (pinfunction "PC4_33") (pintype "bidirectional"))
    )
    (net (code "75") (name "unconnected-(STMI-PC5-Pad34)") (class "Default")
      (node (ref "STM") (pin "34") (pinfunction "PC5_34") (pintype "bidirectional"))
    )
    (net (code "76") (name "unconnected-(STMJ-PD11-Pad58)") (class "Default")
      (node (ref "STM") (pin "58") (pinfunction "PD11_58") (pintype "bidirectional"))
    )
    (net (code "77") (name "unconnected-(STMK-PD0-Pad81)") (class "Default")
      (node (ref "STM") (pin "81") (pinfunction "PD0_81") (pintype "bidirectional"))
    )
    (net (code "78") (name "unconnected-(STMK-PD1-Pad82)") (class "Default")
      (node (ref "STM") (pin "82") (pinfunction "PD1_82") (pintype "bidirectional"))
    )
    (net (code "79") (name "unconnected-(STMK-PD3-Pad84)") (class "Default")
      (node (ref "STM") (pin "84") (pinfunction "PD3_84") (pintype "bidirectional"))
    )
    (net (code "80") (name "unconnected-(STMK-PD4-Pad85)") (class "Default")
      (node (ref "STM") (pin "85") (pinfunction "PD4_85") (pintype "bidirectional"))
    )
    (net (code "81") (name "unconnected-(STMK-PD5-Pad86)") (class "Default")
      (node (ref "STM") (pin "86") (pinfunction "PD5_86") (pintype "bidirectional"))
    )
    (net (code "82") (name "unconnected-(STMK-PD6-Pad87)") (class "Default")
      (node (ref "STM") (pin "87") (pinfunction "PD6_87") (pintype "bidirectional"))
    )
    (net (code "83") (name "unconnected-(STMK-PD7-Pad88)") (class "Default")
      (node (ref "STM") (pin "88") (pinfunction "PD7_88") (pintype "bidirectional"))
    )
    (net (code "84") (name "unconnected-(STML-PE8-Pad39)") (class "Default")
      (node (ref "STM") (pin "39") (pinfunction "PE8_39") (pintype "bidirectional"))
    )
    (net (code "85") (name "unconnected-(STML-PE9-Pad40)") (class "Default")
      (node (ref "STM") (pin "40") (pinfunction "PE9_40") (pintype "bidirectional"))
    )
    (net (code "86") (name "unconnected-(STML-PE10-Pad41)") (class "Default")
      (node (ref "STM") (pin "41") (pinfunction "PE10_41") (pintype "bidirectional"))
    )
    (net (code "87") (name "unconnected-(STML-PE11-Pad42)") (class "Default")
      (node (ref "STM") (pin "42") (pinfunction "PE11_42") (pintype "bidirectional"))
    )
    (net (code "88") (name "unconnected-(STML-PE12-Pad43)") (class "Default")
      (node (ref "STM") (pin "43") (pinfunction "PE12_43") (pintype "bidirectional"))
    )
    (net (code "89") (name "unconnected-(STML-PE13-Pad44)") (class "Default")
      (node (ref "STM") (pin "44") (pinfunction "PE13_44") (pintype "bidirectional"))
    )
    (net (code "90") (name "unconnected-(STML-PE14-Pad45)") (class "Default")
      (node (ref "STM") (pin "45") (pinfunction "PE14_45") (pintype "bidirectional"))
    )
    (net (code "91") (name "unconnected-(STML-PE15-Pad46)") (class "Default")
      (node (ref "STM") (pin "46") (pinfunction "PE15_46") (pintype "bidirectional"))
    )
    (net (code "92") (name "unconnected-(STMM-PE0-Pad97)") (class "Default")
      (node (ref "STM") (pin "97") (pinfunction "PE0_97") (pintype "bidirectional"))
    )
    (net (code "93") (name "unconnected-(STMM-PE1-Pad98)") (class "Default")
      (node (ref "STM") (pin "98") (pinfunction "PE1_98") (pintype "bidirectional"))
    )
    (net (code "94") (name "unconnected-(STMM-PE2-Pad1)") (class "Default")
      (node (ref "STM") (pin "1") (pinfunction "PE2_1") (pintype "bidirectional"))
    )
    (net (code "95") (name "unconnected-(STMM-PE3-Pad2)") (class "Default")
      (node (ref "STM") (pin "2") (pinfunction "PE3_2") (pintype "bidirectional"))
    )
    (net (code "96") (name "unconnected-(STMM-PE4-Pad3)") (class "Default")
      (node (ref "STM") (pin "3") (pinfunction "PE4_3") (pintype "bidirectional"))
    )
    (net (code "97") (name "unconnected-(STMM-PE7-Pad38)") (class "Default")
      (node (ref "STM") (pin "38") (pinfunction "PE7_38") (pintype "bidirectional"))
    )
    (net (code "98") (name "unconnected-(U$1-VDD-Pad1)") (class "Default")
      (node (ref "U$1") (pin "1") (pinfunction "VDD_1") (pintype "bidirectional"))
    )
    (net (code "99") (name "unconnected-(U1-AIO0-Pad9)") (class "Default")
      (node (ref "U1") (pin "9") (pinfunction "AIO0_9") (pintype "bidirectional"))
    )
    (net (code "100") (name "unconnected-(U1-AIO1-Pad10)") (class "Default")
      (node (ref "U1") (pin "10") (pinfunction "AIO1_10") (pintype "bidirectional"))
    )
    (net (code "101") (name "unconnected-(U1-CLK-Pad19)") (class "Default")
      (node (ref "U1") (pin "19") (pinfunction "CLK_19") (pintype "bidirectional"))
    )
    (net (code "102") (name "unconnected-(U1-CSB-Pad16)") (class "Default")
      (node (ref "U1") (pin "16") (pinfunction "CSB_16") (pintype "bidirectional"))
    )
    (net (code "103") (name "unconnected-(U1-CTS-Pad3)") (class "Default")
      (node (ref "U1") (pin "3") (pinfunction "CTS_3") (pintype "bidirectional"))
    )
    (net (code "104") (name "unconnected-(U1-GND1-Pad21)") (class "Default")
      (node (ref "U1") (pin "21") (pinfunction "GND1_21") (pintype "bidirectional"))
    )
    (net (code "105") (name "unconnected-(U1-MISO-Pad18)") (class "Default")
      (node (ref "U1") (pin "18") (pinfunction "MISO_18") (pintype "bidirectional"))
    )
    (net (code "106") (name "unconnected-(U1-MOSI-Pad17)") (class "Default")
      (node (ref "U1") (pin "17") (pinfunction "MOSI_17") (pintype "bidirectional"))
    )
    (net (code "107") (name "unconnected-(U1-NC-Pad14)") (class "Default")
      (node (ref "U1") (pin "14") (pinfunction "NC_14") (pintype "bidirectional"))
    )
    (net (code "108") (name "unconnected-(U1-PCM_CLK-Pad5)") (class "Default")
      (node (ref "U1") (pin "5") (pinfunction "PCM_CLK_5") (pintype "bidirectional"))
    )
    (net (code "109") (name "unconnected-(U1-PCM_IN-Pad7)") (class "Default")
      (node (ref "U1") (pin "7") (pinfunction "PCM_IN_7") (pintype "bidirectional"))
    )
    (net (code "110") (name "unconnected-(U1-PCM_OUT-Pad6)") (class "Default")
      (node (ref "U1") (pin "6") (pinfunction "PCM_OUT_6") (pintype "bidirectional"))
    )
    (net (code "111") (name "unconnected-(U1-PCN_SYNC-Pad8)") (class "Default")
      (node (ref "U1") (pin "8") (pinfunction "PCN_SYNC_8") (pintype "bidirectional"))
    )
    (net (code "112") (name "unconnected-(U1-PIO0-Pad23)") (class "Default")
      (node (ref "U1") (pin "23") (pinfunction "PIO0_23") (pintype "bidirectional"))
    )
    (net (code "113") (name "unconnected-(U1-PIO1-Pad24)") (class "Default")
      (node (ref "U1") (pin "24") (pinfunction "PIO1_24") (pintype "bidirectional"))
    )
    (net (code "114") (name "unconnected-(U1-PIO2-Pad25)") (class "Default")
      (node (ref "U1") (pin "25") (pinfunction "PIO2_25") (pintype "bidirectional"))
    )
    (net (code "115") (name "unconnected-(U1-PIO3-Pad26)") (class "Default")
      (node (ref "U1") (pin "26") (pinfunction "PIO3_26") (pintype "bidirectional"))
    )
    (net (code "116") (name "unconnected-(U1-PIO4-Pad27)") (class "Default")
      (node (ref "U1") (pin "27") (pinfunction "PIO4_27") (pintype "bidirectional"))
    )
    (net (code "117") (name "unconnected-(U1-PIO5-Pad28)") (class "Default")
      (node (ref "U1") (pin "28") (pinfunction "PIO5_28") (pintype "bidirectional"))
    )
    (net (code "118") (name "unconnected-(U1-PIO6-Pad29)") (class "Default")
      (node (ref "U1") (pin "29") (pinfunction "PIO6_29") (pintype "bidirectional"))
    )
    (net (code "119") (name "unconnected-(U1-PIO7-Pad30)") (class "Default")
      (node (ref "U1") (pin "30") (pinfunction "PIO7_30") (pintype "bidirectional"))
    )
    (net (code "120") (name "unconnected-(U1-PIO8-Pad31)") (class "Default")
      (node (ref "U1") (pin "31") (pinfunction "PIO8_31") (pintype "bidirectional"))
    )
    (net (code "121") (name "unconnected-(U1-PIO9-Pad32)") (class "Default")
      (node (ref "U1") (pin "32") (pinfunction "PIO9_32") (pintype "bidirectional"))
    )
    (net (code "122") (name "unconnected-(U1-PIO10-Pad33)") (class "Default")
      (node (ref "U1") (pin "33") (pinfunction "PIO10_33") (pintype "bidirectional"))
    )
    (net (code "123") (name "unconnected-(U1-RST-Pad11)") (class "Default")
      (node (ref "U1") (pin "11") (pinfunction "RST_11") (pintype "bidirectional"))
    )
    (net (code "124") (name "unconnected-(U1-RTS-Pad4)") (class "Default")
      (node (ref "U1") (pin "4") (pinfunction "RTS_4") (pintype "bidirectional"))
    )
    (net (code "125") (name "unconnected-(U1-VBUSD+-Pad20)") (class "Default")
      (node (ref "U1") (pin "20") (pinfunction "VBUSD+_20") (pintype "bidirectional"))
    )
    (net (code "126") (name "unconnected-(U1-VBUSD--Pad15)") (class "Default")
      (node (ref "U1") (pin "15") (pinfunction "VBUSD-_15") (pintype "bidirectional"))
    )
  )
)
